# USB2514_CRYSTAL.net
KiCad netlist of a schematic drawn in Altium Designer
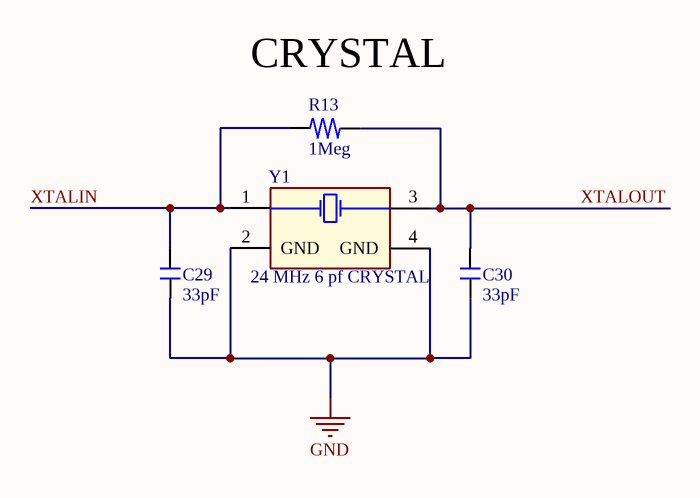
[diagram p0: USB2514 CRYSTAL.SchDoc]

(export (version "E")
  (design (tool "Eeschema 10.0.6"))
  (components
    (comp (ref "C29")
      (value "33pF")
      (footprint "CAPC1608X06N-0603")
      (libsource (lib "SCH_LIB") (part "CAP_0603_0.1uF"))
    )
    (comp (ref "C30")
      (value "33pF")
      (footprint "CAPC1608X06N-0603")
      (libsource (lib "SCH_LIB") (part "CAP_0603_0.1uF"))
    )
    (comp (ref "R13")
      (value "1Meg")
      (footprint "RESC1608X06N-0603")
      (libsource (lib "SCH_LIB") (part "RES_0603_1K"))
    )
    (comp (ref "Y1")
      (value "24 MHz 6 pf CRYSTAL")
      (footprint "OSC_XRCGB24M000F2P00R0")
      (description "8 MHz 12.5 pf Osc")
      (libsource (lib "SCH_LIB") (part "24 MHz 6 pf CRYSTAL"))
    )
  )
  (nets
    (net (code "1") (name "/XTALIN") (class "Default")
      (node (ref "C29") (pin "2") (pinfunction "2_2") (pintype "passive"))
      (node (ref "R13") (pin "1") (pinfunction "1_1") (pintype "passive"))
      (node (ref "Y1") (pin "1") (pintype "power_in"))
    )
    (net (code "2") (name "/XTALOUT") (class "Default")
      (node (ref "C30") (pin "2") (pinfunction "2_2") (pintype "passive"))
      (node (ref "R13") (pin "2") (pinfunction "2_2") (pintype "passive"))
      (node (ref "Y1") (pin "3") (pintype "passive"))
    )
    (net (code "3") (name "GND") (class "Default")
      (node (ref "C29") (pin "1") (pinfunction "1_1") (pintype "passive"))
      (node (ref "C30") (pin "1") (pinfunction "1_1") (pintype "passive"))
      (node (ref "Y1") (pin "2") (pinfunction "GND_2") (pintype "power_in"))
      (node (ref "Y1") (pin "4") (pinfunction "GND_4") (pintype "passive"))
    )
  )
)
